# DAC-v1.net
KiCad netlist of a schematic drawn in EAGLE
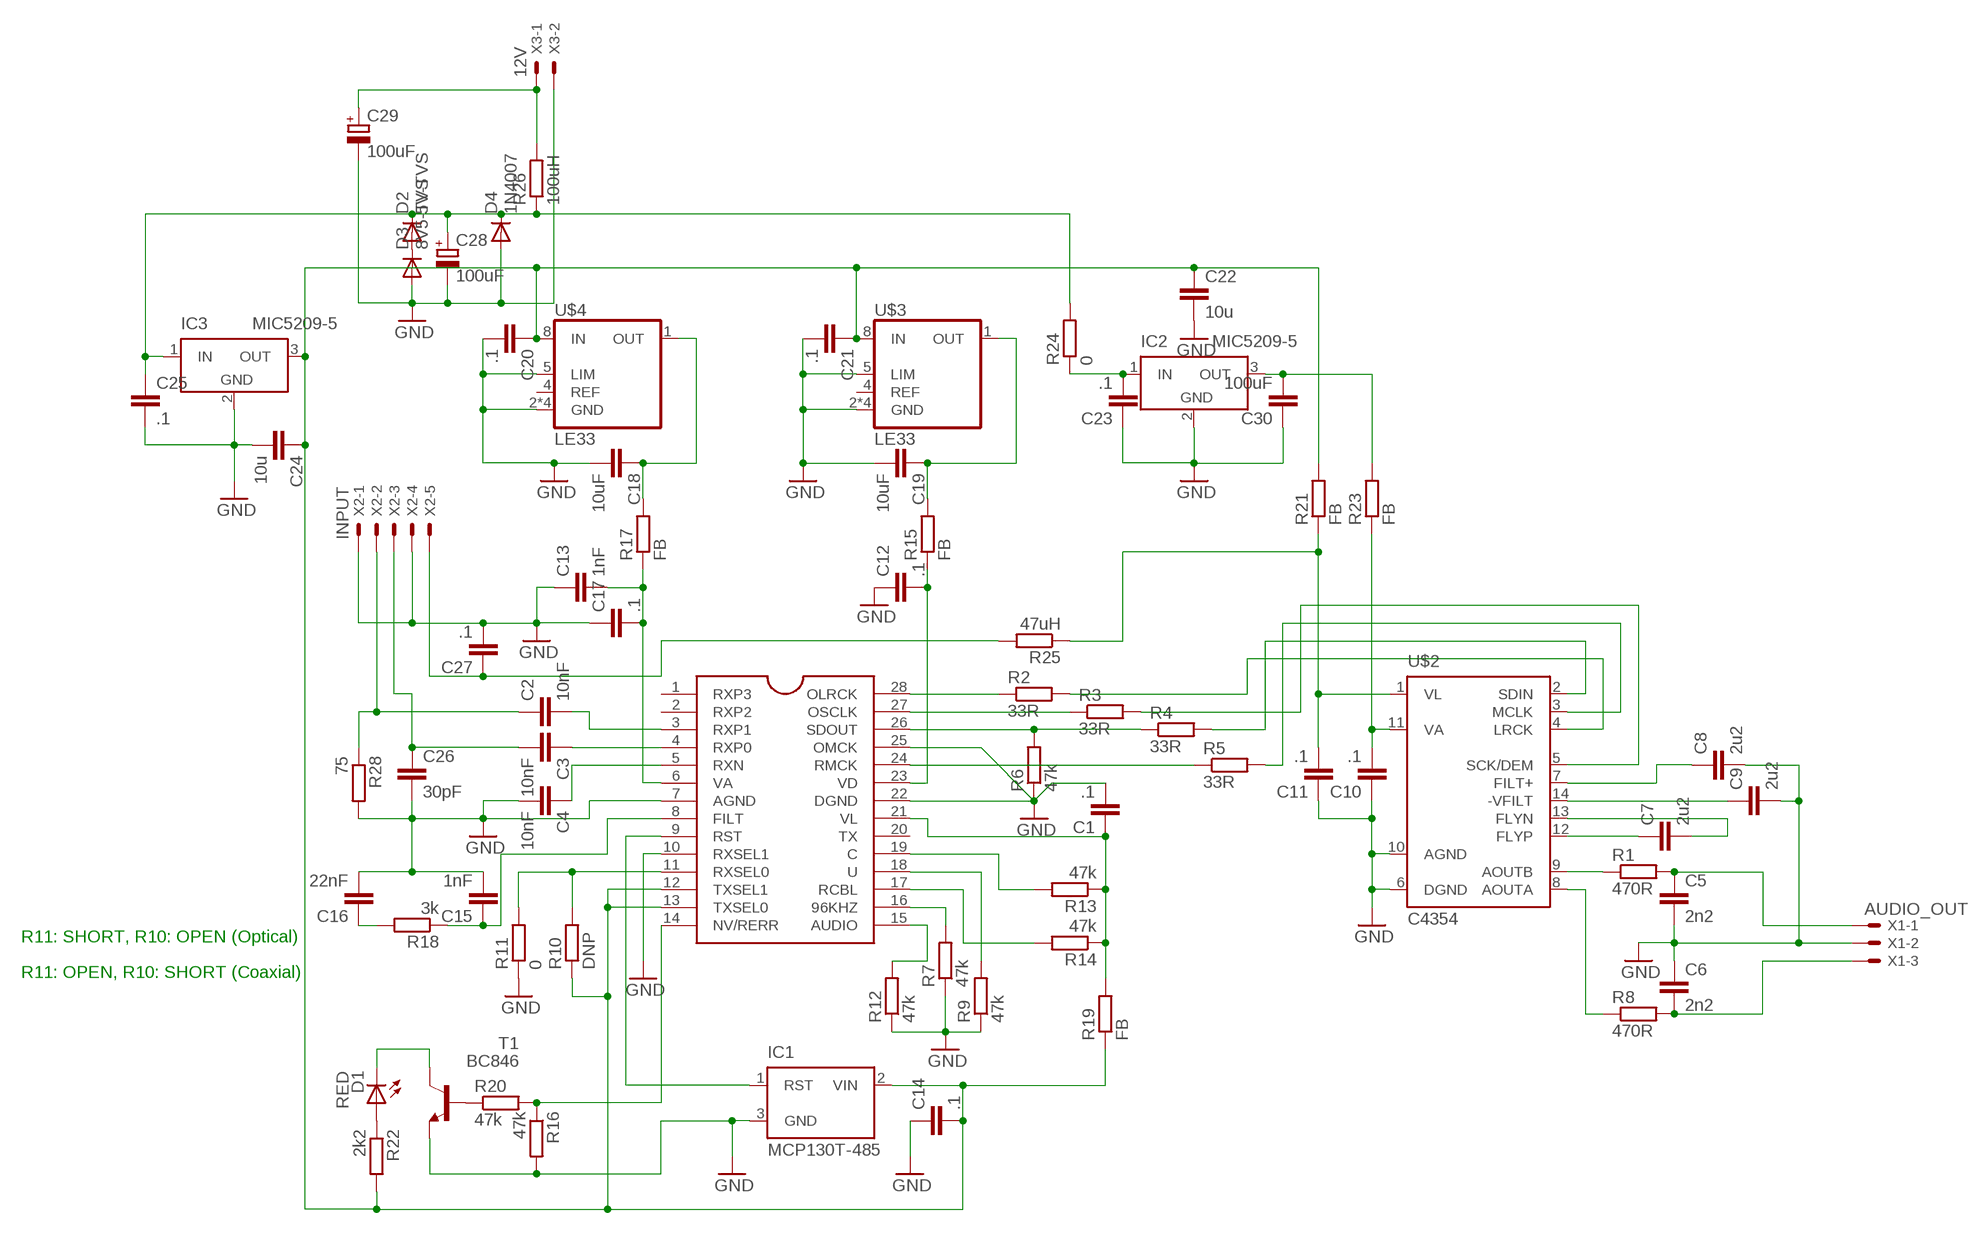
[diagram p0: schematic, sheet 1]

(export (version "E")
  (design (tool "Eeschema 10.0.6"))
  (components
    (comp (ref "C1")
      (value ".1")
      (footprint "eagle-import:C1206")
      (libsource (lib "eagle-import") (part "C-EUC1206"))
    )
    (comp (ref "C2")
      (value "10nF")
      (footprint "eagle-import:C1206")
      (libsource (lib "eagle-import") (part "C-EUC1206"))
    )
    (comp (ref "C3")
      (value "10nF")
      (footprint "eagle-import:C1206")
      (libsource (lib "eagle-import") (part "C-EUC1206"))
    )
    (comp (ref "C4")
      (value "10nF")
      (footprint "eagle-import:C1206")
      (libsource (lib "eagle-import") (part "C-EUC1206"))
    )
    (comp (ref "C5")
      (value "2n2")
      (footprint "eagle-import:C1210")
      (libsource (lib "eagle-import") (part "C-EUC1210"))
    )
    (comp (ref "C6")
      (value "2n2")
      (footprint "eagle-import:C1210")
      (libsource (lib "eagle-import") (part "C-EUC1210"))
    )
    (comp (ref "C7")
      (value "2u2")
      (footprint "eagle-import:C1210")
      (libsource (lib "eagle-import") (part "C-EUC1210"))
    )
    (comp (ref "C8")
      (value "2u2")
      (footprint "eagle-import:C1210")
      (libsource (lib "eagle-import") (part "C-EUC1210"))
    )
    (comp (ref "C9")
      (value "2u2")
      (footprint "eagle-import:C1210")
      (libsource (lib "eagle-import") (part "C-EUC1210"))
    )
    (comp (ref "C10")
      (value ".1")
      (footprint "eagle-import:C1210")
      (libsource (lib "eagle-import") (part "C-EUC1210"))
    )
    (comp (ref "C11")
      (value ".1")
      (footprint "eagle-import:C1210")
      (libsource (lib "eagle-import") (part "C-EUC1210"))
    )
    (comp (ref "C12")
      (value ".1")
      (footprint "eagle-import:C0805")
      (libsource (lib "eagle-import") (part "C-EUC0805"))
    )
    (comp (ref "C13")
      (value "1nF")
      (footprint "eagle-import:C1206")
      (libsource (lib "eagle-import") (part "C-EUC1206"))
    )
    (comp (ref "C14")
      (value ".1")
      (footprint "eagle-import:C0805")
      (libsource (lib "eagle-import") (part "C-EUC0805"))
    )
    (comp (ref "C15")
      (value "1nF")
      (footprint "eagle-import:C0805")
      (libsource (lib "eagle-import") (part "C-EUC0805"))
    )
    (comp (ref "C16")
      (value "22nF")
      (footprint "eagle-import:C0805")
      (libsource (lib "eagle-import") (part "C-EUC0805"))
    )
    (comp (ref "C17")
      (value ".1")
      (footprint "eagle-import:C0805")
      (libsource (lib "eagle-import") (part "C-EUC0805"))
    )
    (comp (ref "C18")
      (value "10uF")
      (footprint "eagle-import:C1206")
      (libsource (lib "eagle-import") (part "C-EUC1206"))
    )
    (comp (ref "C19")
      (value "10uF")
      (footprint "eagle-import:C1206")
      (libsource (lib "eagle-import") (part "C-EUC1206"))
    )
    (comp (ref "C20")
      (value ".1")
      (footprint "eagle-import:C0805")
      (libsource (lib "eagle-import") (part "C-EUC0805"))
    )
    (comp (ref "C21")
      (value ".1")
      (footprint "eagle-import:C0805")
      (libsource (lib "eagle-import") (part "C-EUC0805"))
    )
    (comp (ref "C22")
      (value "10u")
      (footprint "eagle-import:C1210")
      (libsource (lib "eagle-import") (part "C-EUC1210"))
    )
    (comp (ref "C23")
      (value ".1")
      (footprint "eagle-import:C1210")
      (libsource (lib "eagle-import") (part "C-EUC1210"))
    )
    (comp (ref "C24")
      (value "10u")
      (footprint "eagle-import:C1210")
      (libsource (lib "eagle-import") (part "C-EUC1210"))
    )
    (comp (ref "C25")
      (value ".1")
      (footprint "eagle-import:C1210")
      (libsource (lib "eagle-import") (part "C-EUC1210"))
    )
    (comp (ref "C26")
      (value "30pF")
      (footprint "eagle-import:C1206")
      (libsource (lib "eagle-import") (part "C-EUC1206"))
    )
    (comp (ref "C27")
      (value ".1")
      (footprint "eagle-import:C0805")
      (libsource (lib "eagle-import") (part "C-EUC0805"))
    )
    (comp (ref "C28")
      (value "100uF")
      (footprint "eagle-import:E2,5-7")
      (libsource (lib "eagle-import") (part "CPOL-EUE2.5-7"))
    )
    (comp (ref "C29")
      (value "100uF")
      (footprint "eagle-import:E2,5-7")
      (libsource (lib "eagle-import") (part "CPOL-EUE2.5-7"))
    )
    (comp (ref "C30")
      (value "100uF")
      (footprint "eagle-import:C1812K")
      (libsource (lib "eagle-import") (part "C-EUC1812K"))
    )
    (comp (ref "D1")
      (value "RED")
      (footprint "eagle-import:SFH482")
      (libsource (lib "eagle-import") (part "SFH482"))
    )
    (comp (ref "D2")
      (value "5V-TVS")
      (footprint "eagle-import:DO204-10")
      (libsource (lib "eagle-import") (part "1N5059"))
    )
    (comp (ref "D3")
      (value "8V5-TVS")
      (footprint "eagle-import:DO204-10")
      (libsource (lib "eagle-import") (part "1N5059"))
    )
    (comp (ref "D4")
      (value "1N4007")
      (footprint "eagle-import:DO41-10")
      (libsource (lib "eagle-import") (part "1N4004"))
    )
    (comp (ref "IC1")
      (value "MCP130T-485")
      (footprint "eagle-import:SOT23")
      (libsource (lib "eagle-import") (part "MC15TT"))
    )
    (comp (ref "IC2")
      (value "MIC5209-5")
      (footprint "eagle-import:SOT223")
      (fields (field (name "MPN") "LT1129CST-5#PBF"))
      (libsource (lib "eagle-import") (part "LT1129CST5"))
    )
    (comp (ref "IC3")
      (value "MIC5209-5")
      (footprint "eagle-import:SOT223")
      (fields (field (name "MPN") "LT1129CST-5#PBF"))
      (libsource (lib "eagle-import") (part "LT1129CST5"))
    )
    (comp (ref "R1")
      (value "470R")
      (footprint "eagle-import:R0805")
      (libsource (lib "eagle-import") (part "R-EU_R0805"))
    )
    (comp (ref "R2")
      (value "33R")
      (footprint "eagle-import:0204_7")
      (libsource (lib "eagle-import") (part "R-EU_0204/7"))
    )
    (comp (ref "R3")
      (value "33R")
      (footprint "eagle-import:0204_7")
      (libsource (lib "eagle-import") (part "R-EU_0204/7"))
    )
    (comp (ref "R4")
      (value "33R")
      (footprint "eagle-import:R1206")
      (libsource (lib "eagle-import") (part "R-EU_R1206"))
    )
    (comp (ref "R5")
      (value "33R")
      (footprint "eagle-import:R1206")
      (libsource (lib "eagle-import") (part "R-EU_R1206"))
    )
    (comp (ref "R6")
      (value "47k")
      (footprint "eagle-import:R1206")
      (libsource (lib "eagle-import") (part "R-EU_R1206"))
    )
    (comp (ref "R7")
      (value "47k")
      (footprint "eagle-import:R1206")
      (libsource (lib "eagle-import") (part "R-EU_R1206"))
    )
    (comp (ref "R8")
      (value "470R")
      (footprint "eagle-import:R0805")
      (libsource (lib "eagle-import") (part "R-EU_R0805"))
    )
    (comp (ref "R9")
      (value "47k")
      (footprint "eagle-import:R1206")
      (libsource (lib "eagle-import") (part "R-EU_R1206"))
    )
    (comp (ref "R10")
      (value "DNP")
      (footprint "eagle-import:R1206")
      (libsource (lib "eagle-import") (part "R-EU_R1206"))
    )
    (comp (ref "R11")
      (value "0")
      (footprint "eagle-import:R1206")
      (libsource (lib "eagle-import") (part "R-EU_R1206"))
    )
    (comp (ref "R12")
      (value "47k")
      (footprint "eagle-import:R1206")
      (libsource (lib "eagle-import") (part "R-EU_R1206"))
    )
    (comp (ref "R13")
      (value "47k")
      (footprint "eagle-import:R1206")
      (libsource (lib "eagle-import") (part "R-EU_R1206"))
    )
    (comp (ref "R14")
      (value "47k")
      (footprint "eagle-import:R1206")
      (libsource (lib "eagle-import") (part "R-EU_R1206"))
    )
    (comp (ref "R15")
      (value "FB")
      (footprint "eagle-import:R1206")
      (libsource (lib "eagle-import") (part "R-EU_R1206"))
    )
    (comp (ref "R16")
      (value "47k")
      (footprint "eagle-import:R1206")
      (libsource (lib "eagle-import") (part "R-EU_R1206"))
    )
    (comp (ref "R17")
      (value "FB")
      (footprint "eagle-import:R1206")
      (libsource (lib "eagle-import") (part "R-EU_R1206"))
    )
    (comp (ref "R18")
      (value "3k")
      (footprint "eagle-import:R0805")
      (libsource (lib "eagle-import") (part "R-EU_R0805"))
    )
    (comp (ref "R19")
      (value "FB")
      (footprint "eagle-import:R1206")
      (libsource (lib "eagle-import") (part "R-EU_R1206"))
    )
    (comp (ref "R20")
      (value "47k")
      (footprint "eagle-import:R1206")
      (libsource (lib "eagle-import") (part "R-EU_R1206"))
    )
    (comp (ref "R21")
      (value "FB")
      (footprint "eagle-import:R1206")
      (libsource (lib "eagle-import") (part "R-EU_R1206"))
    )
    (comp (ref "R22")
      (value "2k2")
      (footprint "eagle-import:R1206")
      (libsource (lib "eagle-import") (part "R-EU_R1206"))
    )
    (comp (ref "R23")
      (value "FB")
      (footprint "eagle-import:R1206")
      (libsource (lib "eagle-import") (part "R-EU_R1206"))
    )
    (comp (ref "R24")
      (value "0")
      (footprint "eagle-import:0204_7")
      (libsource (lib "eagle-import") (part "R-EU_0204/7"))
    )
    (comp (ref "R25")
      (value "47uH")
      (footprint "eagle-import:R1206")
      (libsource (lib "eagle-import") (part "R-EU_R1206"))
    )
    (comp (ref "R26")
      (value "100uH")
      (footprint "eagle-import:0309_12")
      (libsource (lib "eagle-import") (part "R-EU_0309/12"))
    )
    (comp (ref "R28")
      (value "75")
      (footprint "eagle-import:R0805")
      (libsource (lib "eagle-import") (part "R-EU_R0805"))
    )
    (comp (ref "T1")
      (value "BC846")
      (footprint "eagle-import:SOT23")
      (libsource (lib "eagle-import") (part "BC846"))
    )
    (comp (ref "U$1")
      (value "CS8416")
      (footprint "eagle-import:SO28L")
      (libsource (lib "eagle-import") (part "CS8416-HARDWAREMODEHARDWAREMODE"))
    )
    (comp (ref "U$2")
      (value "C4354")
      (footprint "eagle-import:SO-14")
      (libsource (lib "eagle-import") (part "C4354"))
    )
    (comp (ref "U$3")
      (value "LE33")
      (footprint "eagle-import:SO-08")
      (libsource (lib "eagle-import") (part "LE33"))
    )
    (comp (ref "U$4")
      (value "LE33")
      (footprint "eagle-import:SO-08")
      (libsource (lib "eagle-import") (part "LE33"))
    )
    (comp (ref "X1")
      (value "AUDIO_OUT")
      (footprint "eagle-import:22-23-2031")
      (fields (field (name "MF") "MOLEX") (field (name "MPN") "22-23-2031"))
      (libsource (lib "eagle-import") (part "22-23-2031"))
    )
    (comp (ref "X2")
      (value "INPUT")
      (footprint "eagle-import:22-23-2051")
      (fields (field (name "MF") "MOLEX") (field (name "MPN") "22-23-2051"))
      (libsource (lib "eagle-import") (part "22-23-2051"))
    )
    (comp (ref "X3")
      (value "12V")
      (footprint "eagle-import:22-23-2021")
      (fields (field (name "MF") "MOLEX") (field (name "MPN") "22-23-2021"))
      (libsource (lib "eagle-import") (part "22-23-2021"))
    )
  )
  (nets
    (net (code "1") (name "GND") (class "Default")
      (node (ref "C1") (pin "2") (pinfunction "2_2") (pintype "passive"))
      (node (ref "C10") (pin "1") (pinfunction "1_1") (pintype "passive"))
      (node (ref "C11") (pin "1") (pinfunction "1_1") (pintype "passive"))
      (node (ref "C12") (pin "1") (pinfunction "1_1") (pintype "passive"))
      (node (ref "C13") (pin "1") (pinfunction "1_1") (pintype "passive"))
      (node (ref "C14") (pin "1") (pinfunction "1_1") (pintype "passive"))
      (node (ref "C15") (pin "2") (pinfunction "2_2") (pintype "passive"))
      (node (ref "C16") (pin "2") (pinfunction "2_2") (pintype "passive"))
      (node (ref "C17") (pin "1") (pinfunction "1_1") (pintype "passive"))
      (node (ref "C18") (pin "2") (pinfunction "2_2") (pintype "passive"))
      (node (ref "C19") (pin "2") (pinfunction "2_2") (pintype "passive"))
      (node (ref "C20") (pin "2") (pinfunction "2_2") (pintype "passive"))
      (node (ref "C21") (pin "2") (pinfunction "2_2") (pintype "passive"))
      (node (ref "C22") (pin "2") (pinfunction "2_2") (pintype "passive"))
      (node (ref "C23") (pin "1") (pinfunction "1_1") (pintype "passive"))
      (node (ref "C24") (pin "2") (pinfunction "2_2") (pintype "passive"))
      (node (ref "C25") (pin "2") (pinfunction "2_2") (pintype "passive"))
      (node (ref "C26") (pin "2") (pinfunction "2_2") (pintype "passive"))
      (node (ref "C27") (pin "2") (pinfunction "2_2") (pintype "passive"))
      (node (ref "C28") (pin "-") (pinfunction "-_-") (pintype "passive"))
      (node (ref "C29") (pin "-") (pinfunction "-_-") (pintype "passive"))
      (node (ref "C30") (pin "1") (pinfunction "1_1") (pintype "passive"))
      (node (ref "C4") (pin "2") (pinfunction "2_2") (pintype "passive"))
      (node (ref "C5") (pin "2") (pinfunction "2_2") (pintype "passive"))
      (node (ref "C6") (pin "1") (pinfunction "1_1") (pintype "passive"))
      (node (ref "C8") (pin "2") (pinfunction "2_2") (pintype "passive"))
      (node (ref "C9") (pin "2") (pinfunction "2_2") (pintype "passive"))
      (node (ref "D3") (pin "A") (pinfunction "A_A") (pintype "passive"))
      (node (ref "D4") (pin "A") (pinfunction "A_A") (pintype "passive"))
      (node (ref "IC1") (pin "3") (pinfunction "GND_3") (pintype "passive"))
      (node (ref "IC2") (pin "2") (pinfunction "GND_2") (pintype "power_in"))
      (node (ref "IC3") (pin "2") (pinfunction "GND_2") (pintype "power_in"))
      (node (ref "R11") (pin "1") (pinfunction "1_1") (pintype "passive"))
      (node (ref "R12") (pin "1") (pinfunction "1_1") (pintype "passive"))
      (node (ref "R16") (pin "2") (pinfunction "2_2") (pintype "passive"))
      (node (ref "R28") (pin "2") (pinfunction "2_2") (pintype "passive"))
      (node (ref "R6") (pin "1") (pinfunction "1_1") (pintype "passive"))
      (node (ref "R7") (pin "1") (pinfunction "1_1") (pintype "passive"))
      (node (ref "R9") (pin "1") (pinfunction "1_1") (pintype "passive"))
      (node (ref "T1") (pin "2") (pinfunction "E_2") (pintype "passive"))
      (node (ref "U$1") (pin "10") (pinfunction "RXSEL1_10") (pintype "bidirectional"))
      (node (ref "U$1") (pin "22") (pinfunction "DGND_22") (pintype "bidirectional"))
      (node (ref "U$1") (pin "25") (pinfunction "OMCK_25") (pintype "bidirectional"))
      (node (ref "U$1") (pin "7") (pinfunction "AGND_7") (pintype "bidirectional"))
      (node (ref "U$2") (pin "10") (pinfunction "AGND_10") (pintype "power_in"))
      (node (ref "U$2") (pin "6") (pinfunction "DGND_6") (pintype "power_in"))
      (node (ref "U$3") (pin "2") (pinfunction "GND_2") (pintype "passive"))
      (node (ref "U$3") (pin "3") (pinfunction "GND_3") (pintype "passive"))
      (node (ref "U$3") (pin "5") (pinfunction "LIM_5") (pintype "input"))
      (node (ref "U$3") (pin "6") (pinfunction "GND_6") (pintype "passive"))
      (node (ref "U$3") (pin "7") (pinfunction "GND_7") (pintype "passive"))
      (node (ref "U$4") (pin "2") (pinfunction "GND_2") (pintype "passive"))
      (node (ref "U$4") (pin "3") (pinfunction "GND_3") (pintype "passive"))
      (node (ref "U$4") (pin "5") (pinfunction "LIM_5") (pintype "input"))
      (node (ref "U$4") (pin "6") (pinfunction "GND_6") (pintype "passive"))
      (node (ref "U$4") (pin "7") (pinfunction "GND_7") (pintype "passive"))
      (node (ref "X1") (pin "2") (pinfunction "S_2") (pintype "passive"))
      (node (ref "X2") (pin "1") (pinfunction "S_1") (pintype "passive"))
      (node (ref "X2") (pin "4") (pinfunction "S_4") (pintype "passive"))
      (node (ref "X3") (pin "2") (pinfunction "S_2") (pintype "passive"))
    )
    (net (code "2") (name "Net-(C16-Pad1)") (class "Default")
      (node (ref "C16") (pin "1") (pinfunction "1_1") (pintype "passive"))
      (node (ref "R18") (pin "2") (pinfunction "2_2") (pintype "passive"))
    )
    (net (code "3") (name "Net-(D1-C)") (class "Default")
      (node (ref "D1") (pin "K") (pinfunction "C_K") (pintype "passive"))
      (node (ref "T1") (pin "3") (pinfunction "C_3") (pintype "passive"))
    )
    (net (code "4") (name "Net-(D1-PadA)") (class "Default")
      (node (ref "D1") (pin "A") (pinfunction "A_A") (pintype "passive"))
      (node (ref "R22") (pin "1") (pinfunction "1_1") (pintype "passive"))
    )
    (net (code "5") (name "Net-(D2-PadA)") (class "Default")
      (node (ref "D2") (pin "A") (pinfunction "A_A") (pintype "passive"))
      (node (ref "D3") (pin "C") (pinfunction "C_C") (pintype "passive"))
    )
    (net (code "6") (name "Net-(IC1-RST)") (class "Default")
      (node (ref "IC1") (pin "1") (pinfunction "RST_1") (pintype "input"))
      (node (ref "U$1") (pin "9") (pinfunction "RST_9") (pintype "bidirectional"))
    )
    (net (code "7") (name "Net-(IC1-VIN)") (class "Default")
      (node (ref "C14") (pin "2") (pinfunction "2_2") (pintype "passive"))
      (node (ref "C20") (pin "1") (pinfunction "1_1") (pintype "passive"))
      (node (ref "C21") (pin "1") (pinfunction "1_1") (pintype "passive"))
      (node (ref "C22") (pin "1") (pinfunction "1_1") (pintype "passive"))
      (node (ref "C24") (pin "1") (pinfunction "1_1") (pintype "passive"))
      (node (ref "IC1") (pin "2") (pinfunction "VIN_2") (pintype "output"))
      (node (ref "IC3") (pin "3") (pinfunction "OUT_3") (pintype "output"))
      (node (ref "R10") (pin "1") (pinfunction "1_1") (pintype "passive"))
      (node (ref "R19") (pin "1") (pinfunction "1_1") (pintype "passive"))
      (node (ref "R21") (pin "2") (pinfunction "2_2") (pintype "passive"))
      (node (ref "R22") (pin "2") (pinfunction "2_2") (pintype "passive"))
      (node (ref "U$1") (pin "12") (pinfunction "TXSEL1_12") (pintype "bidirectional"))
      (node (ref "U$1") (pin "13") (pinfunction "TXSEL0_13") (pintype "bidirectional"))
      (node (ref "U$3") (pin "8") (pinfunction "IN_8") (pintype "input"))
      (node (ref "U$4") (pin "8") (pinfunction "IN_8") (pintype "input"))
    )
    (net (code "8") (name "Net-(IC2A-IN)") (class "Default")
      (node (ref "C23") (pin "2") (pinfunction "2_2") (pintype "passive"))
      (node (ref "IC2") (pin "1") (pinfunction "IN_1") (pintype "input"))
      (node (ref "R24") (pin "1") (pinfunction "1_1") (pintype "passive"))
    )
    (net (code "9") (name "Net-(IC2A-OUT)") (class "Default")
      (node (ref "C30") (pin "2") (pinfunction "2_2") (pintype "passive"))
      (node (ref "IC2") (pin "3") (pinfunction "OUT_3") (pintype "output"))
      (node (ref "R23") (pin "2") (pinfunction "2_2") (pintype "passive"))
    )
    (net (code "10") (name "Net-(IC3A-IN)") (class "Default")
      (node (ref "C25") (pin "1") (pinfunction "1_1") (pintype "passive"))
      (node (ref "C28") (pin "+") (pinfunction "+_+") (pintype "passive"))
      (node (ref "D2") (pin "C") (pinfunction "C_C") (pintype "passive"))
      (node (ref "D4") (pin "C") (pinfunction "C_C") (pintype "passive"))
      (node (ref "IC3") (pin "1") (pinfunction "IN_1") (pintype "input"))
      (node (ref "R24") (pin "2") (pinfunction "2_2") (pintype "passive"))
      (node (ref "R26") (pin "1") (pinfunction "1_1") (pintype "passive"))
    )
    (net (code "11") (name "Net-(T1-B)") (class "Default")
      (node (ref "R20") (pin "1") (pinfunction "1_1") (pintype "passive"))
      (node (ref "T1") (pin "1") (pinfunction "B_1") (pintype "passive"))
    )
    (net (code "12") (name "Net-(U$1-96KHZ)") (class "Default")
      (node (ref "R7") (pin "2") (pinfunction "2_2") (pintype "passive"))
      (node (ref "U$1") (pin "16") (pinfunction "96KHZ_16") (pintype "bidirectional"))
    )
    (net (code "13") (name "Net-(U$1-AUDIO)") (class "Default")
      (node (ref "R12") (pin "2") (pinfunction "2_2") (pintype "passive"))
      (node (ref "U$1") (pin "15") (pinfunction "AUDIO_15") (pintype "bidirectional"))
    )
    (net (code "14") (name "Net-(U$1-C)") (class "Default")
      (node (ref "R13") (pin "2") (pinfunction "2_2") (pintype "passive"))
      (node (ref "U$1") (pin "19") (pinfunction "C_19") (pintype "bidirectional"))
    )
    (net (code "15") (name "Net-(U$1-FILT)") (class "Default")
      (node (ref "C15") (pin "1") (pinfunction "1_1") (pintype "passive"))
      (node (ref "R18") (pin "1") (pinfunction "1_1") (pintype "passive"))
      (node (ref "U$1") (pin "8") (pinfunction "FILT_8") (pintype "bidirectional"))
    )
    (net (code "16") (name "Net-(U$1-NV{slash}RERR)") (class "Default")
      (node (ref "R16") (pin "1") (pinfunction "1_1") (pintype "passive"))
      (node (ref "R20") (pin "2") (pinfunction "2_2") (pintype "passive"))
      (node (ref "U$1") (pin "14") (pinfunction "NV/RERR_14") (pintype "bidirectional"))
    )
    (net (code "17") (name "Net-(U$1-OLRCK)") (class "Default")
      (node (ref "R2") (pin "1") (pinfunction "1_1") (pintype "passive"))
      (node (ref "U$1") (pin "28") (pinfunction "OLRCK_28") (pintype "bidirectional"))
    )
    (net (code "18") (name "Net-(U$1-OSCLK)") (class "Default")
      (node (ref "R3") (pin "1") (pinfunction "1_1") (pintype "passive"))
      (node (ref "U$1") (pin "27") (pinfunction "OSCLK_27") (pintype "bidirectional"))
    )
    (net (code "19") (name "Net-(U$1-RCBL)") (class "Default")
      (node (ref "R14") (pin "2") (pinfunction "2_2") (pintype "passive"))
      (node (ref "U$1") (pin "17") (pinfunction "RCBL_17") (pintype "bidirectional"))
    )
    (net (code "20") (name "Net-(U$1-RMCK)") (class "Default")
      (node (ref "R5") (pin "1") (pinfunction "1_1") (pintype "passive"))
      (node (ref "U$1") (pin "24") (pinfunction "RMCK_24") (pintype "bidirectional"))
    )
    (net (code "21") (name "Net-(U$1-RXN)") (class "Default")
      (node (ref "C4") (pin "1") (pinfunction "1_1") (pintype "passive"))
      (node (ref "U$1") (pin "5") (pinfunction "RXN_5") (pintype "bidirectional"))
    )
    (net (code "22") (name "Net-(U$1-RXP0)") (class "Default")
      (node (ref "C3") (pin "1") (pinfunction "1_1") (pintype "passive"))
      (node (ref "U$1") (pin "4") (pinfunction "RXP0_4") (pintype "bidirectional"))
    )
    (net (code "23") (name "Net-(U$1-RXP1)") (class "Default")
      (node (ref "C2") (pin "2") (pinfunction "2_2") (pintype "passive"))
      (node (ref "U$1") (pin "3") (pinfunction "RXP1_3") (pintype "bidirectional"))
    )
    (net (code "24") (name "Net-(U$1-RXSEL0)") (class "Default")
      (node (ref "R10") (pin "2") (pinfunction "2_2") (pintype "passive"))
      (node (ref "R11") (pin "2") (pinfunction "2_2") (pintype "passive"))
      (node (ref "U$1") (pin "11") (pinfunction "RXSEL0_11") (pintype "bidirectional"))
    )
    (net (code "25") (name "Net-(U$1-SDOUT)") (class "Default")
      (node (ref "R4") (pin "1") (pinfunction "1_1") (pintype "passive"))
      (node (ref "R6") (pin "2") (pinfunction "2_2") (pintype "passive"))
      (node (ref "U$1") (pin "26") (pinfunction "SDOUT_26") (pintype "bidirectional"))
    )
    (net (code "26") (name "Net-(U$1-U)") (class "Default")
      (node (ref "R9") (pin "2") (pinfunction "2_2") (pintype "passive"))
      (node (ref "U$1") (pin "18") (pinfunction "U_18") (pintype "bidirectional"))
    )
    (net (code "27") (name "Net-(U$1-VA)") (class "Default")
      (node (ref "C13") (pin "2") (pinfunction "2_2") (pintype "passive"))
      (node (ref "C17") (pin "2") (pinfunction "2_2") (pintype "passive"))
      (node (ref "R17") (pin "1") (pinfunction "1_1") (pintype "passive"))
      (node (ref "U$1") (pin "6") (pinfunction "VA_6") (pintype "bidirectional"))
    )
    (net (code "28") (name "Net-(U$1-VD)") (class "Default")
      (node (ref "C12") (pin "2") (pinfunction "2_2") (pintype "passive"))
      (node (ref "R15") (pin "1") (pinfunction "1_1") (pintype "passive"))
      (node (ref "U$1") (pin "23") (pinfunction "VD_23") (pintype "bidirectional"))
    )
    (net (code "29") (name "Net-(U$1-VL)") (class "Default")
      (node (ref "C1") (pin "1") (pinfunction "1_1") (pintype "passive"))
      (node (ref "R13") (pin "1") (pinfunction "1_1") (pintype "passive"))
      (node (ref "R14") (pin "1") (pinfunction "1_1") (pintype "passive"))
      (node (ref "R19") (pin "2") (pinfunction "2_2") (pintype "passive"))
      (node (ref "U$1") (pin "21") (pinfunction "VL_21") (pintype "bidirectional"))
    )
    (net (code "30") (name "Net-(U$2--VFILT)") (class "Default")
      (node (ref "C9") (pin "1") (pinfunction "1_1") (pintype "passive"))
      (node (ref "U$2") (pin "14") (pinfunction "-VFILT_14") (pintype "input"))
    )
    (net (code "31") (name "Net-(U$2-AOUTA)") (class "Default")
      (node (ref "R8") (pin "1") (pinfunction "1_1") (pintype "passive"))
      (node (ref "U$2") (pin "8") (pinfunction "AOUTA_8") (pintype "bidirectional"))
    )
    (net (code "32") (name "Net-(U$2-AOUTB)") (class "Default")
      (node (ref "R1") (pin "1") (pinfunction "1_1") (pintype "passive"))
      (node (ref "U$2") (pin "9") (pinfunction "AOUTB_9") (pintype "bidirectional"))
    )
    (net (code "33") (name "Net-(U$2-FILT+)") (class "Default")
      (node (ref "C8") (pin "1") (pinfunction "1_1") (pintype "passive"))
      (node (ref "U$2") (pin "7") (pinfunction "FILT+_7") (pintype "input"))
    )
    (net (code "34") (name "Net-(U$2-FLYN)") (class "Default")
      (node (ref "C7") (pin "2") (pinfunction "2_2") (pintype "passive"))
      (node (ref "U$2") (pin "13") (pinfunction "FLYN_13") (pintype "input"))
    )
    (net (code "35") (name "Net-(U$2-FLYP)") (class "Default")
      (node (ref "C7") (pin "1") (pinfunction "1_1") (pintype "passive"))
      (node (ref "U$2") (pin "12") (pinfunction "FLYP_12") (pintype "input"))
    )
    (net (code "36") (name "Net-(U$2-LRCK)") (class "Default")
      (node (ref "R2") (pin "2") (pinfunction "2_2") (pintype "passive"))
      (node (ref "U$2") (pin "4") (pinfunction "LRCK_4") (pintype "bidirectional"))
    )
    (net (code "37") (name "Net-(U$2-MCLK)") (class "Default")
      (node (ref "R5") (pin "2") (pinfunction "2_2") (pintype "passive"))
      (node (ref "U$2") (pin "3") (pinfunction "MCLK_3") (pintype "bidirectional"))
    )
    (net (code "38") (name "Net-(U$2-SCK{slash}DEM)") (class "Default")
      (node (ref "R3") (pin "2") (pinfunction "2_2") (pintype "passive"))
      (node (ref "U$2") (pin "5") (pinfunction "SCK/DEM_5") (pintype "input"))
    )
    (net (code "39") (name "Net-(U$2-SDIN)") (class "Default")
      (node (ref "R4") (pin "2") (pinfunction "2_2") (pintype "passive"))
      (node (ref "U$2") (pin "2") (pinfunction "SDIN_2") (pintype "output"))
    )
    (net (code "40") (name "Net-(U$2-VA)") (class "Default")
      (node (ref "C10") (pin "2") (pinfunction "2_2") (pintype "passive"))
      (node (ref "R23") (pin "1") (pinfunction "1_1") (pintype "passive"))
      (node (ref "U$2") (pin "11") (pinfunction "VA_11") (pintype "input"))
    )
    (net (code "41") (name "Net-(U$2-VL)") (class "Default")
      (node (ref "C11") (pin "2") (pinfunction "2_2") (pintype "passive"))
      (node (ref "R21") (pin "1") (pinfunction "1_1") (pintype "passive"))
      (node (ref "R25") (pin "1") (pinfunction "1_1") (pintype "passive"))
      (node (ref "U$2") (pin "1") (pinfunction "VL_1") (pintype "power_in"))
    )
    (net (code "42") (name "Net-(U$3-OUT)") (class "Default")
      (node (ref "C19") (pin "1") (pinfunction "1_1") (pintype "passive"))
      (node (ref "R15") (pin "2") (pinfunction "2_2") (pintype "passive"))
      (node (ref "U$3") (pin "1") (pinfunction "OUT_1") (pintype "passive"))
    )
    (net (code "43") (name "Net-(U$4-OUT)") (class "Default")
      (node (ref "C18") (pin "1") (pinfunction "1_1") (pintype "passive"))
      (node (ref "R17") (pin "2") (pinfunction "2_2") (pintype "passive"))
      (node (ref "U$4") (pin "1") (pinfunction "OUT_1") (pintype "passive"))
    )
    (net (code "44") (name "Net-(X1A-S)") (class "Default")
      (node (ref "C5") (pin "1") (pinfunction "1_1") (pintype "passive"))
      (node (ref "R1") (pin "2") (pinfunction "2_2") (pintype "passive"))
      (node (ref "X1") (pin "1") (pinfunction "S_1") (pintype "passive"))
    )
    (net (code "45") (name "Net-(X1C-S)") (class "Default")
      (node (ref "C6") (pin "2") (pinfunction "2_2") (pintype "passive"))
      (node (ref "R8") (pin "2") (pinfunction "2_2") (pintype "passive"))
      (node (ref "X1") (pin "3") (pinfunction "S_3") (pintype "passive"))
    )
    (net (code "46") (name "Net-(X2B-S)") (class "Default")
      (node (ref "C2") (pin "1") (pinfunction "1_1") (pintype "passive"))
      (node (ref "R28") (pin "1") (pinfunction "1_1") (pintype "passive"))
      (node (ref "X2") (pin "2") (pinfunction "S_2") (pintype "passive"))
    )
    (net (code "47") (name "Net-(X2C-S)") (class "Default")
      (node (ref "C26") (pin "1") (pinfunction "1_1") (pintype "passive"))
      (node (ref "C3") (pin "2") (pinfunction "2_2") (pintype "passive"))
      (node (ref "X2") (pin "3") (pinfunction "S_3") (pintype "passive"))
    )
    (net (code "48") (name "Net-(X2E-S)") (class "Default")
      (node (ref "C27") (pin "1") (pinfunction "1_1") (pintype "passive"))
      (node (ref "R25") (pin "2") (pinfunction "2_2") (pintype "passive"))
      (node (ref "X2") (pin "5") (pinfunction "S_5") (pintype "passive"))
    )
    (net (code "49") (name "Net-(X3A-S)") (class "Default")
      (node (ref "C29") (pin "+") (pinfunction "+_+") (pintype "passive"))
      (node (ref "R26") (pin "2") (pinfunction "2_2") (pintype "passive"))
      (node (ref "X3") (pin "1") (pinfunction "S_1") (pintype "passive"))
    )
    (net (code "50") (name "unconnected-(U$1-RXP2-Pad2)") (class "Default")
      (node (ref "U$1") (pin "2") (pinfunction "RXP2_2") (pintype "bidirectional"))
    )
    (net (code "51") (name "unconnected-(U$1-RXP3-Pad1)") (class "Default")
      (node (ref "U$1") (pin "1") (pinfunction "RXP3_1") (pintype "bidirectional"))
    )
    (net (code "52") (name "unconnected-(U$1-TX-Pad20)") (class "Default")
      (node (ref "U$1") (pin "20") (pinfunction "TX_20") (pintype "bidirectional"))
    )
    (net (code "53") (name "unconnected-(U$3-REF-Pad4)") (class "Default")
      (node (ref "U$3") (pin "4") (pinfunction "REF_4") (pintype "input"))
    )
    (net (code "54") (name "unconnected-(U$4-REF-Pad4)") (class "Default")
      (node (ref "U$4") (pin "4") (pinfunction "REF_4") (pintype "input"))
    )
  )
)
